# Virtual-Ground.net
KiCad netlist of a schematic drawn in EAGLE
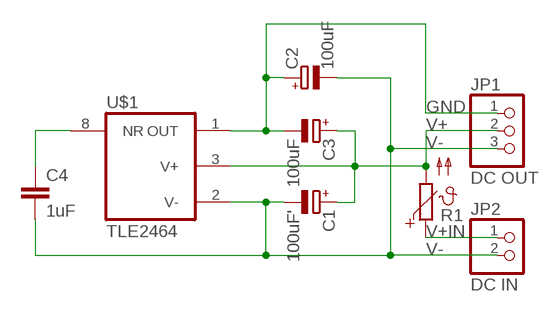
[diagram p0: schematic, sheet 1]

(export (version "E")
  (design (tool "Eeschema 10.0.6"))
  (components
    (comp (ref "C1")
      (value "100uF'")
      (footprint "eagle-import:E2,5-6")
      (libsource (lib "eagle-import") (part "CPOL-EUE2.5-6"))
    )
    (comp (ref "C2")
      (value "100uF")
      (footprint "eagle-import:E2,5-6")
      (libsource (lib "eagle-import") (part "CPOL-EUE2.5-6"))
    )
    (comp (ref "C3")
      (value "100uF")
      (footprint "eagle-import:E2,5-6")
      (libsource (lib "eagle-import") (part "CPOL-EUE2.5-6"))
    )
    (comp (ref "C4")
      (value "1uF")
      (footprint "eagle-import:C050-050X075")
      (libsource (lib "eagle-import") (part "C-EU050-050X075"))
    )
    (comp (ref "JP1")
      (value "DC OUT")
      (footprint "eagle-import:1X03")
      (libsource (lib "eagle-import") (part "PINHD-1X3"))
    )
    (comp (ref "JP2")
      (value "DC IN")
      (footprint "eagle-import:1X02")
      (libsource (lib "eagle-import") (part "PINHD-1X2"))
    )
    (comp (ref "R1")
      (value "PTC660")
      (footprint "eagle-import:P660")
      (libsource (lib "eagle-import") (part "PTC660"))
    )
    (comp (ref "U$1")
      (value "TLE2464")
      (footprint "eagle-import:TLE2464")
      (libsource (lib "eagle-import") (part "TLE2464"))
    )
  )
  (nets
    (net (code "1") (name "/GND") (class "Default")
      (node (ref "C2") (pin "+") (pinfunction "+_+") (pintype "passive"))
      (node (ref "C3") (pin "-") (pinfunction "-_-") (pintype "passive"))
      (node (ref "JP1") (pin "1") (pinfunction "1_1") (pintype "passive"))
      (node (ref "U$1") (pin "1") (pinfunction "OUT_1") (pintype "output"))
    )
    (net (code "2") (name "/V+") (class "Default")
      (node (ref "C1") (pin "+") (pinfunction "+_+") (pintype "passive"))
      (node (ref "C3") (pin "+") (pinfunction "+_+") (pintype "passive"))
      (node (ref "JP1") (pin "2") (pinfunction "2_2") (pintype "passive"))
      (node (ref "R1") (pin "2") (pinfunction "2_2") (pintype "passive"))
      (node (ref "U$1") (pin "3") (pinfunction "V+_3") (pintype "power_in"))
    )
    (net (code "3") (name "/V+IN") (class "Default")
      (node (ref "JP2") (pin "1") (pinfunction "1_1") (pintype "passive"))
      (node (ref "R1") (pin "1") (pinfunction "1_1") (pintype "passive"))
    )
    (net (code "4") (name "/V-") (class "Default")
      (node (ref "C1") (pin "-") (pinfunction "-_-") (pintype "passive"))
      (node (ref "C2") (pin "-") (pinfunction "-_-") (pintype "passive"))
      (node (ref "C4") (pin "2") (pinfunction "2_2") (pintype "passive"))
      (node (ref "JP1") (pin "3") (pinfunction "3_3") (pintype "passive"))
      (node (ref "JP2") (pin "2") (pinfunction "2_2") (pintype "passive"))
      (node (ref "U$1") (pin "2") (pinfunction "V-_2") (pintype "power_in"))
    )
    (net (code "5") (name "Net-(U$1-NR)") (class "Default")
      (node (ref "C4") (pin "1") (pinfunction "1_1") (pintype "passive"))
      (node (ref "U$1") (pin "8") (pinfunction "NR_8") (pintype "input"))
    )
  )
)
